# LED_DriverR3.net
KiCad netlist of a schematic drawn in Altium Designer
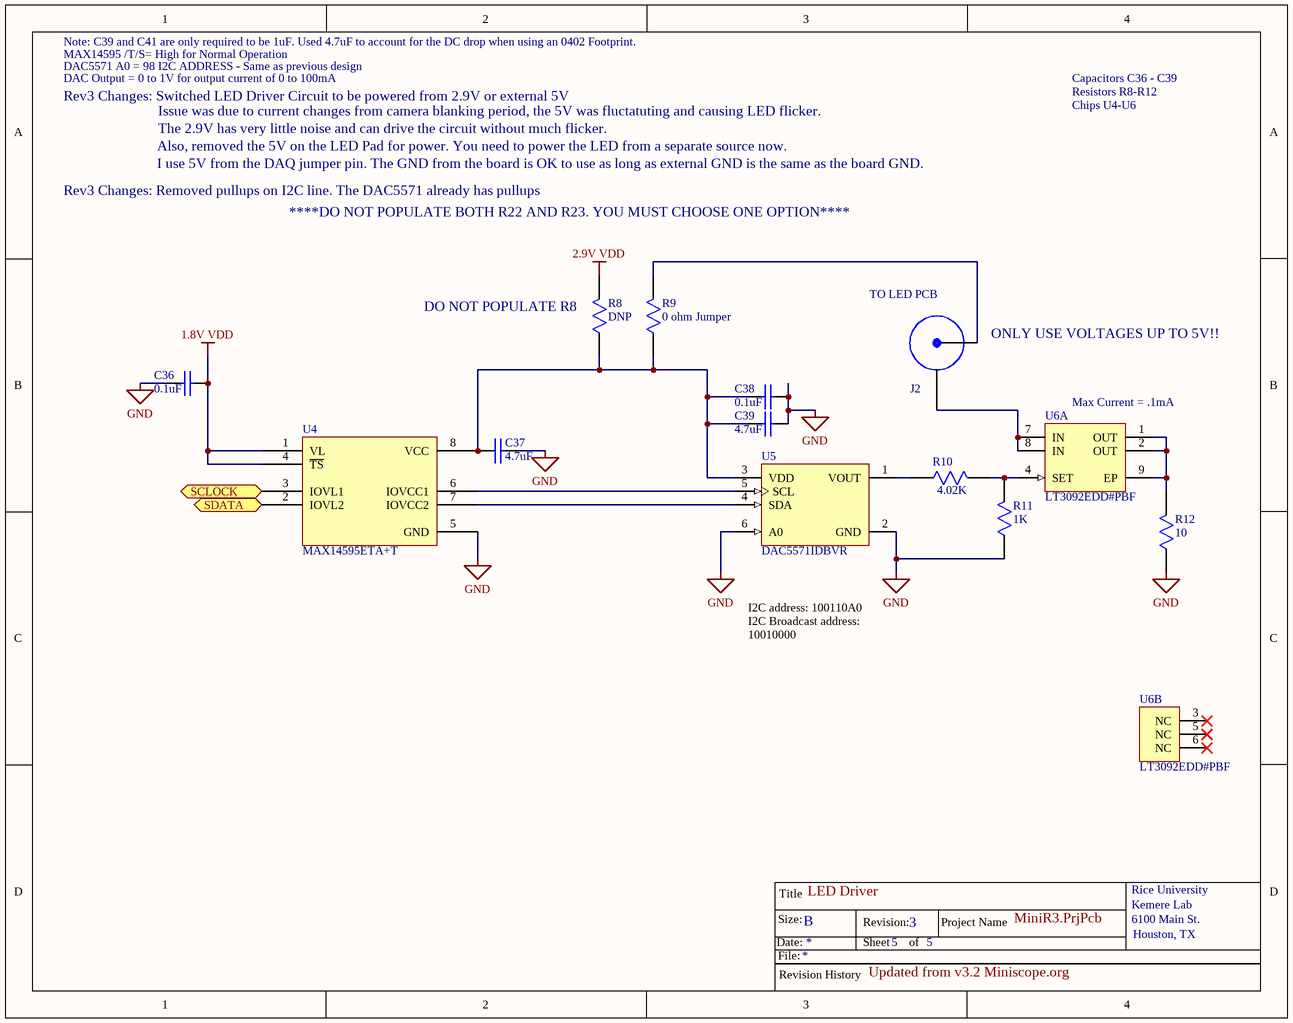
[diagram p0: LED_DriverR3.SchDoc]

(export (version "E")
  (design (tool "Eeschema 10.0.6"))
  (components
    (comp (ref "C36")
      (value "0.1uF")
      (footprint "SMD CAP 0402")
      (libsource (lib "DA_Component_Library") (part "Capacitor"))
    )
    (comp (ref "C37")
      (value "4.7uF")
      (footprint "SMD CAP 0402")
      (libsource (lib "DA_Component_Library") (part "Capacitor"))
    )
    (comp (ref "C38")
      (value "0.1uF")
      (footprint "SMD CAP 0402")
      (libsource (lib "DA_Component_Library") (part "Capacitor"))
    )
    (comp (ref "C39")
      (value "4.7uF")
      (footprint "SMD CAP 0402")
      (libsource (lib "DA_Component_Library") (part "Capacitor"))
    )
    (comp (ref "J2")
      (value "Coax Connector")
      (footprint "Coax Direct Solder ThroughHoles")
      (libsource (lib "DA_Component_Library") (part "Coax Connector"))
    )
    (comp (ref "R8")
      (value "DNP")
      (footprint "SMD RES 0402")
      (libsource (lib "DA_Component_Library") (part "Resistor"))
    )
    (comp (ref "R9")
      (value "0 ohm Jumper")
      (footprint "SMD RES 0402")
      (libsource (lib "DA_Component_Library") (part "Resistor"))
    )
    (comp (ref "R10")
      (value "4.02K")
      (footprint "SMD RES 0402")
      (libsource (lib "DA_Component_Library") (part "Resistor"))
    )
    (comp (ref "R11")
      (value "1K")
      (footprint "SMD RES 0402")
      (libsource (lib "DA_Component_Library") (part "Resistor"))
    )
    (comp (ref "R12")
      (value "10")
      (footprint "SMD RES 0402")
      (libsource (lib "DA_Component_Library") (part "Resistor"))
    )
    (comp (ref "U4")
      (value "MAX14595ETA+T")
      (footprint "8 TDFN")
      (description "Level Translator")
      (libsource (lib "Miniscope") (part "MAX14595ETA+T"))
    )
    (comp (ref "U5") (value "DAC5571IDBVR") (footprint "DBV") (libsource (lib "Miniscope") (part "DAC5571")))
    (comp (ref "U6")
      (value "LT3092EDD#PBF")
      (footprint "LT-DD-8_V")
      (fields (field (name "MANUFACTURER") "Linear Technology"))
      (libsource (lib "DA_Component_Library") (part "LT3092EDD#PBF"))
    )
  )
  (nets
    (net (code "1") (name "/SCLOCK") (class "Default")
      (node (ref "U4") (pin "3") (pinfunction "IOVL1_3") (pintype "passive"))
    )
    (net (code "2") (name "/SDATA") (class "Default")
      (node (ref "U4") (pin "2") (pinfunction "IOVL2_2") (pintype "passive"))
    )
    (net (code "3") (name "1.8V VDD") (class "Default")
      (node (ref "C36") (pin "1") (pinfunction "1_1") (pintype "passive"))
      (node (ref "U4") (pin "1") (pinfunction "VL_1") (pintype "passive"))
      (node (ref "U4") (pin "4") (pinfunction "~{TS}_4") (pintype "passive"))
    )
    (net (code "4") (name "2.9V VDD") (class "Default")
      (node (ref "R8") (pin "1") (pinfunction "1_1") (pintype "passive"))
    )
    (net (code "5") (name "GND") (class "Default")
      (node (ref "C36") (pin "0") (pinfunction "0_0") (pintype "passive"))
      (node (ref "C37") (pin "1") (pinfunction "1_1") (pintype "passive"))
      (node (ref "C38") (pin "1") (pinfunction "1_1") (pintype "passive"))
      (node (ref "C39") (pin "1") (pinfunction "1_1") (pintype "passive"))
      (node (ref "R11") (pin "0") (pinfunction "0_0") (pintype "passive"))
      (node (ref "R12") (pin "0") (pinfunction "0_0") (pintype "passive"))
      (node (ref "U4") (pin "5") (pinfunction "GND_5") (pintype "passive"))
      (node (ref "U5") (pin "2") (pinfunction "GND_2") (pintype "power_in"))
      (node (ref "U5") (pin "6") (pinfunction "A0_6") (pintype "input"))
    )
    (net (code "6") (name "Net-(J2-Pad0)") (class "Default")
      (node (ref "J2") (pin "0") (pinfunction "0_0") (pintype "passive"))
      (node (ref "R9") (pin "1") (pinfunction "1_1") (pintype "passive"))
    )
    (net (code "7") (name "Net-(J2-Pad1)") (class "Default")
      (node (ref "J2") (pin "1") (pinfunction "1_1") (pintype "passive"))
      (node (ref "U6") (pin "7") (pinfunction "IN_7") (pintype "power_in"))
      (node (ref "U6") (pin "8") (pinfunction "IN_8") (pintype "power_in"))
    )
    (net (code "8") (name "Net-(U4-IOVCC1)") (class "Default")
      (node (ref "U4") (pin "6") (pinfunction "IOVCC1_6") (pintype "passive"))
      (node (ref "U5") (pin "5") (pinfunction "SCL_5") (pintype "input"))
    )
    (net (code "9") (name "Net-(U4-IOVCC2)") (class "Default")
      (node (ref "U4") (pin "7") (pinfunction "IOVCC2_7") (pintype "passive"))
      (node (ref "U5") (pin "4") (pinfunction "SDA_4") (pintype "input"))
    )
    (net (code "10") (name "Net-(U4-VCC)") (class "Default")
      (node (ref "C37") (pin "0") (pinfunction "0_0") (pintype "passive"))
      (node (ref "C38") (pin "0") (pinfunction "0_0") (pintype "passive"))
      (node (ref "C39") (pin "0") (pinfunction "0_0") (pintype "passive"))
      (node (ref "R8") (pin "0") (pinfunction "0_0") (pintype "passive"))
      (node (ref "R9") (pin "0") (pinfunction "0_0") (pintype "passive"))
      (node (ref "U4") (pin "8") (pinfunction "VCC_8") (pintype "passive"))
      (node (ref "U5") (pin "3") (pinfunction "VDD_3") (pintype "power_in"))
    )
    (net (code "11") (name "Net-(U5-VOUT)") (class "Default")
      (node (ref "R10") (pin "0") (pinfunction "0_0") (pintype "passive"))
      (node (ref "U5") (pin "1") (pinfunction "VOUT_1") (pintype "tri_state"))
    )
    (net (code "12") (name "Net-(U6A-EP)") (class "Default")
      (node (ref "R12") (pin "1") (pinfunction "1_1") (pintype "passive"))
      (node (ref "U6") (pin "1") (pinfunction "OUT_1") (pintype "power_in"))
      (node (ref "U6") (pin "2") (pinfunction "OUT_2") (pintype "power_in"))
      (node (ref "U6") (pin "9") (pinfunction "EP_9") (pintype "power_in"))
    )
    (net (code "13") (name "Net-(U6A-SET)") (class "Default")
      (node (ref "R10") (pin "1") (pinfunction "1_1") (pintype "passive"))
      (node (ref "R11") (pin "1") (pinfunction "1_1") (pintype "passive"))
      (node (ref "U6") (pin "4") (pinfunction "SET_4") (pintype "input"))
    )
    (net (code "14") (name "unconnected-(U6B-NC-Pad3)") (class "Default")
      (node (ref "U6") (pin "3") (pinfunction "NC_3") (pintype "passive+no_connect"))
    )
    (net (code "15") (name "unconnected-(U6B-NC-Pad5)") (class "Default")
      (node (ref "U6") (pin "5") (pinfunction "NC_5") (pintype "passive+no_connect"))
    )
    (net (code "16") (name "unconnected-(U6B-NC-Pad6)") (class "Default")
      (node (ref "U6") (pin "6") (pinfunction "NC_6") (pintype "passive+no_connect"))
    )
  )
)
